# STB_UID.net
KiCad netlist of a schematic drawn in Altium Designer
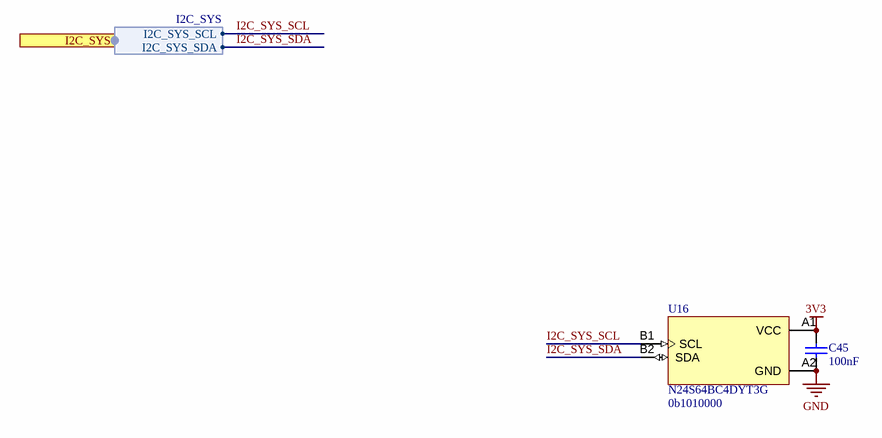
[diagram p0: STB_UID.SchDoc]

(export (version "E")
  (design (tool "Eeschema 10.0.6"))
  (components
    (comp (ref "C45")
      (value "100nF")
      (footprint "CAPC1050X55X23LL05T13")
      (description "Chip Capacitor, 100 nF, +/- 10%, 16 V, -55 to 125 degC, 0402 (1005 Metric), RoHS, Tape and Reel")
      (fields
        (field (name "MANUFACTURER") "Samsung Electro-Mechanics")
        (field (name "MANUFACTURER PART NUMBER") "CL05B104KO5NNNC")
      )
      (libsource (lib "Altium Content Vault") (part "CAP-NP-2"))
    )
    (comp (ref "U16")
      (value "N24S64BC4DYT3G")
      (footprint "4-WLCSP (0.77x0.77)")
      (description "Memory IC 64Kb (8K x 8) I²C 1 MHz 400 ns 4-WLCSP (0.77x0.77)")
      (fields (field (name "MFR") "onsemi") (field (name "MANUFACTURER") "ON Semiconductor"))
      (libsource (lib "ETHZ Vault") (part "N24S64BC4DYT3G"))
    )
  )
  (nets
    (net (code "2") (name "/I2C_SYS_SCL") (class "Default")
      (node (ref "U16") (pin "B1") (pinfunction "SCL_B1") (pintype "input"))
    )
    (net (code "3") (name "/I2C_SYS_SDA") (class "Default")
      (node (ref "U16") (pin "B2") (pinfunction "SDA_B2") (pintype "bidirectional"))
    )
    (net (code "5") (name "3V3") (class "Default")
      (node (ref "C45") (pin "2") (pinfunction "2_2") (pintype "passive"))
      (node (ref "U16") (pin "A1") (pinfunction "VCC_A1") (pintype "power_in"))
    )
    (net (code "6") (name "GND") (class "Default")
      (node (ref "C45") (pin "1") (pinfunction "1_1") (pintype "passive"))
      (node (ref "U16") (pin "A2") (pinfunction "GND_A2") (pintype "power_in"))
    )
  )
)
